# amiga_4player_adapter.net
KiCad netlist of a schematic drawn in EAGLE
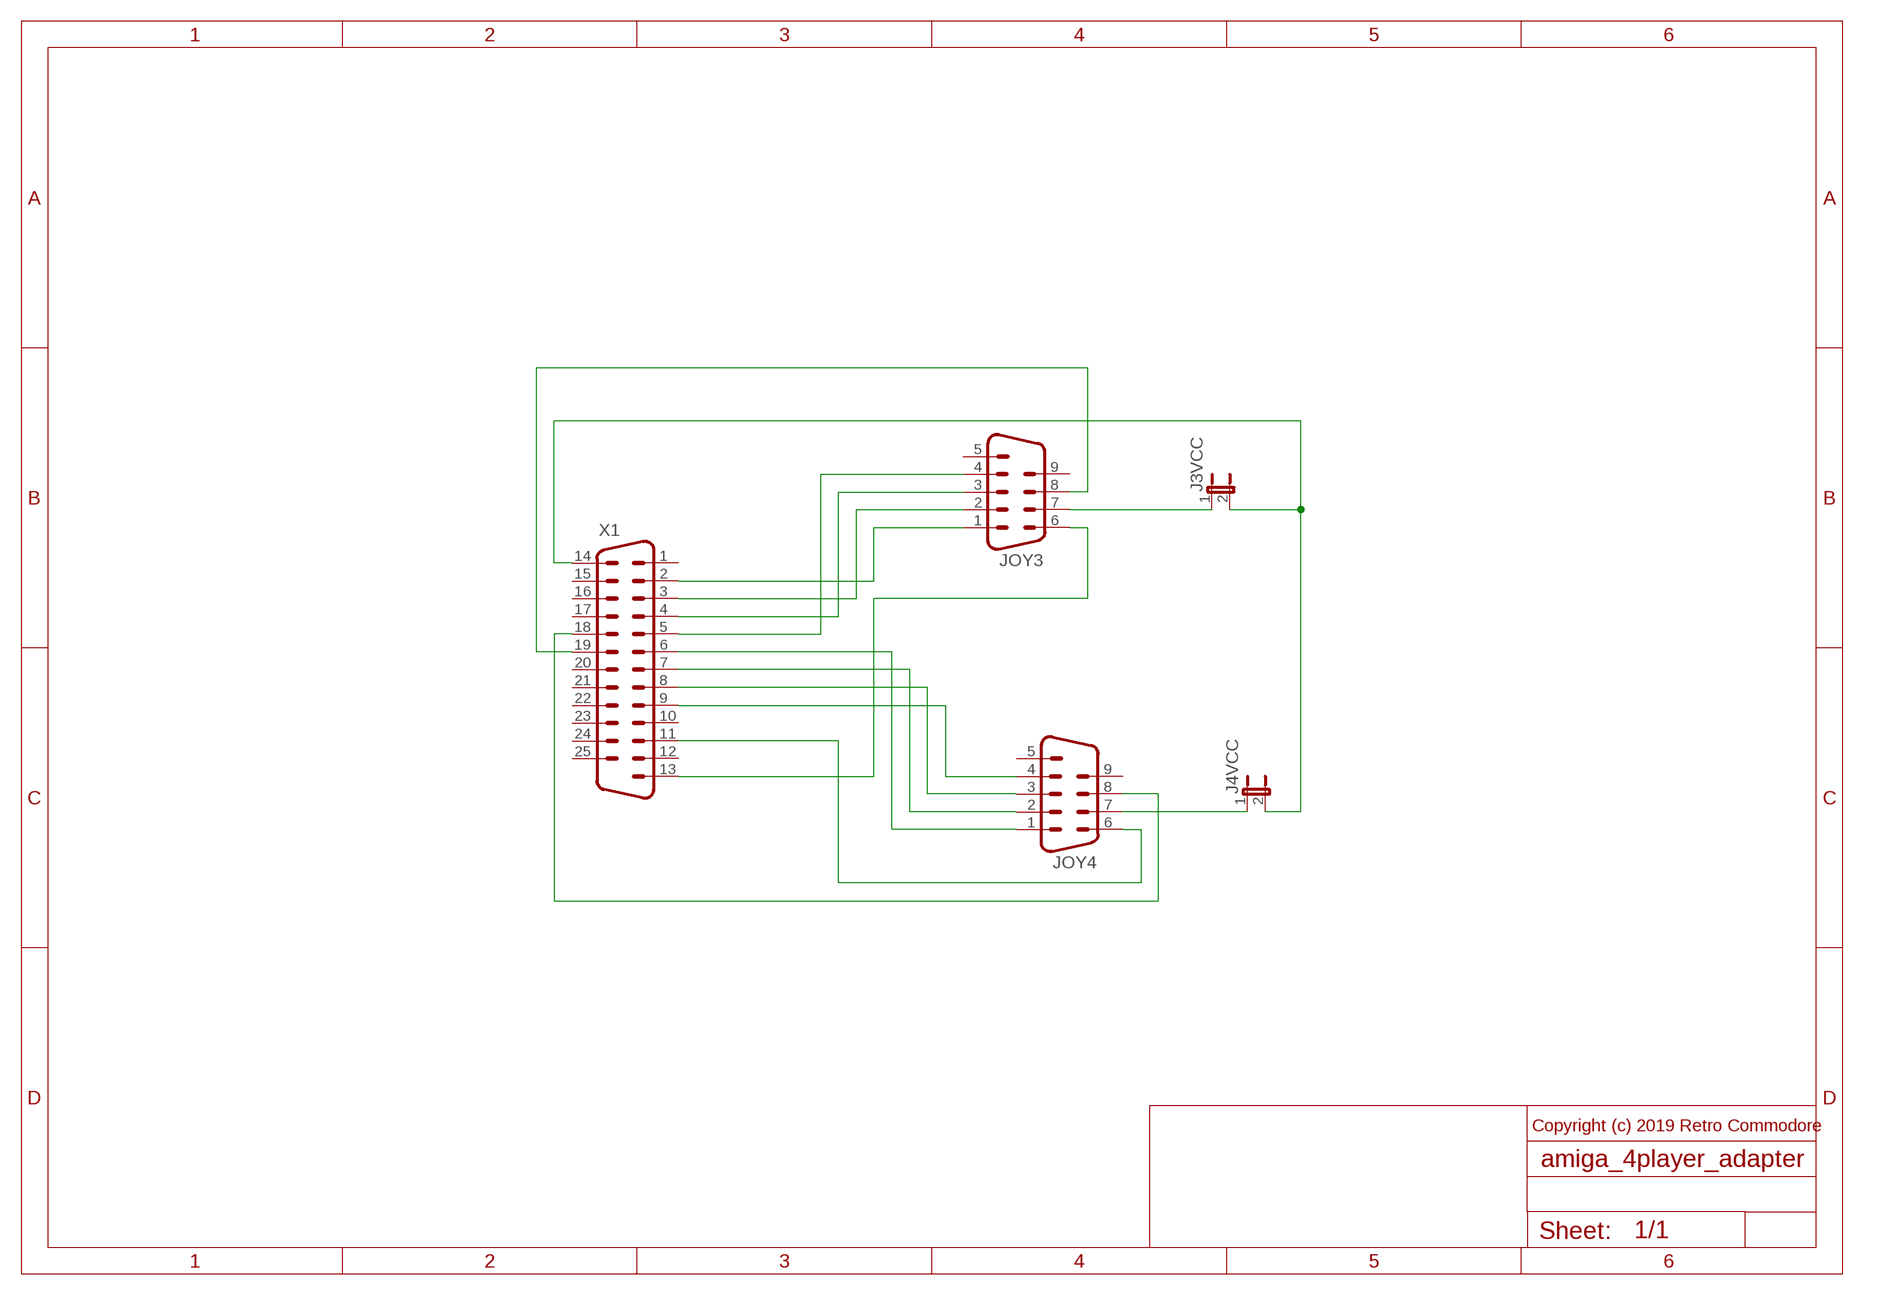
[diagram p0: schematic, sheet 1]

(export (version "E")
  (design (tool "Eeschema 10.0.6"))
  (components
    (comp (ref "J3VCC")
      (value "JP1E")
      (footprint "eagle-import:JP1")
      (libsource (lib "eagle-import") (part "JP1E"))
    )
    (comp (ref "J4VCC")
      (value "JP1E")
      (footprint "eagle-import:JP1")
      (libsource (lib "eagle-import") (part "JP1E"))
    )
    (comp (ref "JOY3")
      (value "M09D")
      (footprint "eagle-import:M09D")
      (libsource (lib "eagle-import") (part "M09D"))
    )
    (comp (ref "JOY4")
      (value "M09D")
      (footprint "eagle-import:M09D")
      (libsource (lib "eagle-import") (part "M09D"))
    )
    (comp (ref "X1")
      (value "M25D")
      (footprint "eagle-import:M25D")
      (libsource (lib "eagle-import") (part "M25D"))
    )
  )
  (nets
    (net (code "1") (name "/GND") (class "Default")
      (node (ref "JOY3") (pin "8") (pinfunction "8_8") (pintype "passive"))
      (node (ref "JOY4") (pin "8") (pinfunction "8_8") (pintype "passive"))
      (node (ref "X1") (pin "18") (pinfunction "18_18") (pintype "passive"))
      (node (ref "X1") (pin "19") (pinfunction "19_19") (pintype "passive"))
    )
    (net (code "2") (name "Net-(J3VCC-Pad1)") (class "Default")
      (node (ref "J3VCC") (pin "1") (pinfunction "1_1") (pintype "passive"))
      (node (ref "JOY3") (pin "7") (pinfunction "7_7") (pintype "passive"))
    )
    (net (code "3") (name "Net-(J3VCC-Pad2)") (class "Default")
      (node (ref "J3VCC") (pin "2") (pinfunction "2_2") (pintype "passive"))
      (node (ref "J4VCC") (pin "2") (pinfunction "2_2") (pintype "passive"))
      (node (ref "X1") (pin "14") (pinfunction "14_14") (pintype "passive"))
    )
    (net (code "4") (name "Net-(J4VCC-Pad1)") (class "Default")
      (node (ref "J4VCC") (pin "1") (pinfunction "1_1") (pintype "passive"))
      (node (ref "JOY4") (pin "7") (pinfunction "7_7") (pintype "passive"))
    )
    (net (code "5") (name "Net-(JOY3-Pad1)") (class "Default")
      (node (ref "JOY3") (pin "1") (pinfunction "1_1") (pintype "passive"))
      (node (ref "X1") (pin "2") (pinfunction "2_2") (pintype "passive"))
    )
    (net (code "6") (name "Net-(JOY3-Pad2)") (class "Default")
      (node (ref "JOY3") (pin "2") (pinfunction "2_2") (pintype "passive"))
      (node (ref "X1") (pin "3") (pinfunction "3_3") (pintype "passive"))
    )
    (net (code "7") (name "Net-(JOY3-Pad3)") (class "Default")
      (node (ref "JOY3") (pin "3") (pinfunction "3_3") (pintype "passive"))
      (node (ref "X1") (pin "4") (pinfunction "4_4") (pintype "passive"))
    )
    (net (code "8") (name "Net-(JOY3-Pad4)") (class "Default")
      (node (ref "JOY3") (pin "4") (pinfunction "4_4") (pintype "passive"))
      (node (ref "X1") (pin "5") (pinfunction "5_5") (pintype "passive"))
    )
    (net (code "9") (name "Net-(JOY3-Pad6)") (class "Default")
      (node (ref "JOY3") (pin "6") (pinfunction "6_6") (pintype "passive"))
      (node (ref "X1") (pin "13") (pinfunction "13_13") (pintype "passive"))
    )
    (net (code "10") (name "Net-(JOY4-Pad1)") (class "Default")
      (node (ref "JOY4") (pin "1") (pinfunction "1_1") (pintype "passive"))
      (node (ref "X1") (pin "6") (pinfunction "6_6") (pintype "passive"))
    )
    (net (code "11") (name "Net-(JOY4-Pad2)") (class "Default")
      (node (ref "JOY4") (pin "2") (pinfunction "2_2") (pintype "passive"))
      (node (ref "X1") (pin "7") (pinfunction "7_7") (pintype "passive"))
    )
    (net (code "12") (name "Net-(JOY4-Pad3)") (class "Default")
      (node (ref "JOY4") (pin "3") (pinfunction "3_3") (pintype "passive"))
      (node (ref "X1") (pin "8") (pinfunction "8_8") (pintype "passive"))
    )
    (net (code "13") (name "Net-(JOY4-Pad4)") (class "Default")
      (node (ref "JOY4") (pin "4") (pinfunction "4_4") (pintype "passive"))
      (node (ref "X1") (pin "9") (pinfunction "9_9") (pintype "passive"))
    )
    (net (code "14") (name "Net-(JOY4-Pad6)") (class "Default")
      (node (ref "JOY4") (pin "6") (pinfunction "6_6") (pintype "passive"))
      (node (ref "X1") (pin "11") (pinfunction "11_11") (pintype "passive"))
    )
    (net (code "15") (name "unconnected-(JOY3-Pad5)") (class "Default")
      (node (ref "JOY3") (pin "5") (pinfunction "5_5") (pintype "passive"))
    )
    (net (code "16") (name "unconnected-(JOY3-Pad9)") (class "Default")
      (node (ref "JOY3") (pin "9") (pinfunction "9_9") (pintype "passive"))
    )
    (net (code "17") (name "unconnected-(JOY4-Pad5)") (class "Default")
      (node (ref "JOY4") (pin "5") (pinfunction "5_5") (pintype "passive"))
    )
    (net (code "18") (name "unconnected-(JOY4-Pad9)") (class "Default")
      (node (ref "JOY4") (pin "9") (pinfunction "9_9") (pintype "passive"))
    )
    (net (code "19") (name "unconnected-(X1-Pad1)") (class "Default")
      (node (ref "X1") (pin "1") (pinfunction "1_1") (pintype "passive"))
    )
    (net (code "20") (name "unconnected-(X1-Pad10)") (class "Default")
      (node (ref "X1") (pin "10") (pinfunction "10_10") (pintype "passive"))
    )
    (net (code "21") (name "unconnected-(X1-Pad12)") (class "Default")
      (node (ref "X1") (pin "12") (pinfunction "12_12") (pintype "passive"))
    )
    (net (code "22") (name "unconnected-(X1-Pad15)") (class "Default")
      (node (ref "X1") (pin "15") (pinfunction "15_15") (pintype "passive"))
    )
    (net (code "23") (name "unconnected-(X1-Pad16)") (class "Default")
      (node (ref "X1") (pin "16") (pinfunction "16_16") (pintype "passive"))
    )
    (net (code "24") (name "unconnected-(X1-Pad17)") (class "Default")
      (node (ref "X1") (pin "17") (pinfunction "17_17") (pintype "passive"))
    )
    (net (code "25") (name "unconnected-(X1-Pad20)") (class "Default")
      (node (ref "X1") (pin "20") (pinfunction "20_20") (pintype "passive"))
    )
    (net (code "26") (name "unconnected-(X1-Pad21)") (class "Default")
      (node (ref "X1") (pin "21") (pinfunction "21_21") (pintype "passive"))
    )
    (net (code "27") (name "unconnected-(X1-Pad22)") (class "Default")
      (node (ref "X1") (pin "22") (pinfunction "22_22") (pintype "passive"))
    )
    (net (code "28") (name "unconnected-(X1-Pad23)") (class "Default")
      (node (ref "X1") (pin "23") (pinfunction "23_23") (pintype "passive"))
    )
    (net (code "29") (name "unconnected-(X1-Pad24)") (class "Default")
      (node (ref "X1") (pin "24") (pinfunction "24_24") (pintype "passive"))
    )
    (net (code "30") (name "unconnected-(X1-Pad25)") (class "Default")
      (node (ref "X1") (pin "25") (pinfunction "25_25") (pintype "passive"))
    )
  )
)
